# quadcopter.net
KiCad netlist of a schematic drawn in EAGLE
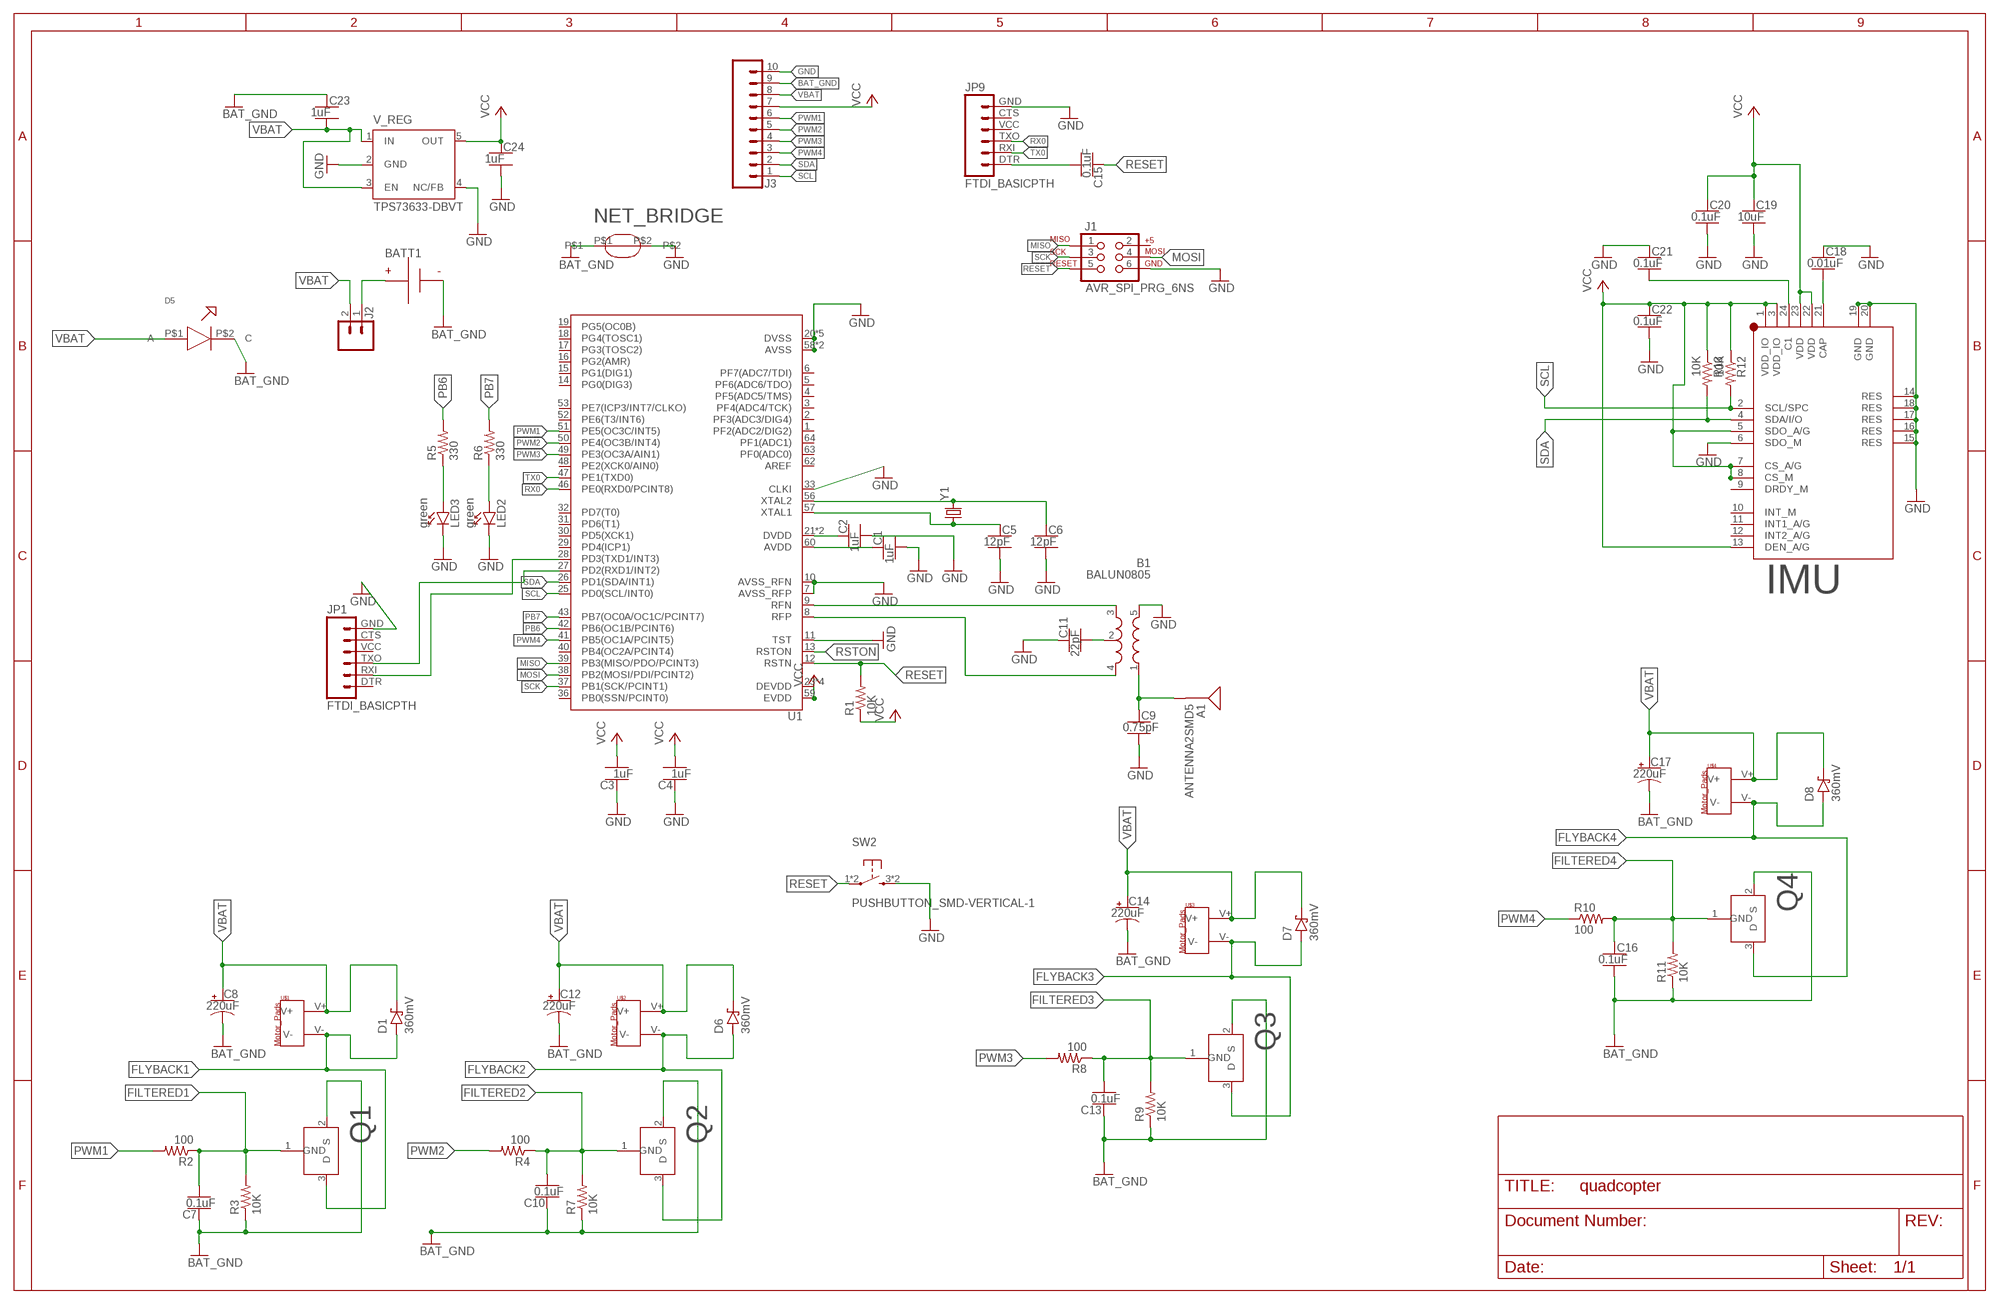
[diagram p0: schematic, sheet 1]

(export (version "E")
  (design (tool "Eeschema 10.0.6"))
  (components
    (comp (ref "A1")
      (value "ANTENNA2SMD5")
      (footprint "eagle-import:ANTENNA-CHIP5")
      (fields (field (name "MFR") "Linx Technologies Inc.") (field (name "MPN") "ANT-2.45-CHP-T"))
      (libsource (lib "eagle-import") (part "ANTENNA2SMD5"))
    )
    (comp (ref "B1")
      (value "BALUN0805")
      (footprint "eagle-import:BALUN")
      (fields (field (name "MFR") "Wurth Electronics Inc") (field (name "MPN") "748421245"))
      (libsource (lib "eagle-import") (part "BALUN0805"))
    )
    (comp (ref "BATT1")
      (value "BATTERY-HUBSAN-W/HOLDER")
      (footprint "eagle-import:BATTERY-W_HOLDER-380MAH-HUBSAN")
      (fields
        (field (name "MFR") "HUBSAN")
        (field (name "MPN") "X4-H107C-8-in-1")
        (field (name "CREATOR") "Swanson")
      )
      (libsource (lib "eagle-import") (part "BATTERY-HUBSAN-W/HOLDER"))
    )
    (comp (ref "C1")
      (value "1uF")
      (footprint "eagle-import:CAPC2012X140_HS")
      (fields
        (field (name "MFR") "Murata Electronics North America")
        (field (name "MPN") "GRM21BR71H105KA12L")
      )
      (libsource (lib "eagle-import") (part "CAPACITOR-NP_SMD-2012-0805_CERAMIC-1UF"))
    )
    (comp (ref "C2")
      (value "1uF")
      (footprint "eagle-import:CAPC2012X140_HS")
      (fields
        (field (name "MFR") "Murata Electronics North America")
        (field (name "MPN") "GRM21BR71H105KA12L")
      )
      (libsource (lib "eagle-import") (part "CAPACITOR-NP_SMD-2012-0805_CERAMIC-1UF"))
    )
    (comp (ref "C3")
      (value "1uF")
      (footprint "eagle-import:CAPC2012X140_HS")
      (fields
        (field (name "MFR") "Murata Electronics North America")
        (field (name "MPN") "GRM21BR71H105KA12L")
      )
      (libsource (lib "eagle-import") (part "CAPACITOR-NP_SMD-2012-0805_CERAMIC-1UF"))
    )
    (comp (ref "C4")
      (value "1uF")
      (footprint "eagle-import:CAPC2012X140_HS")
      (fields
        (field (name "MFR") "Murata Electronics North America")
        (field (name "MPN") "GRM21BR71H105KA12L")
      )
      (libsource (lib "eagle-import") (part "CAPACITOR-NP_SMD-2012-0805_CERAMIC-1UF"))
    )
    (comp (ref "C5")
      (value "12pF")
      (footprint "eagle-import:CAPC2012X140_HS")
      (fields
        (field (name "MFR") "Murata Electronics North America")
        (field (name "MPN") "GRM21A5C2E120JW01D")
      )
      (libsource (lib "eagle-import") (part "CAPACITOR-NP_SMD-2012-0805_CERAMIC-12PF"))
    )
    (comp (ref "C6")
      (value "12pF")
      (footprint "eagle-import:CAPC2012X140_HS")
      (fields
        (field (name "MFR") "Murata Electronics North America")
        (field (name "MPN") "GRM21A5C2E120JW01D")
      )
      (libsource (lib "eagle-import") (part "CAPACITOR-NP_SMD-2012-0805_CERAMIC-12PF"))
    )
    (comp (ref "C7")
      (value "0.1uF")
      (footprint "eagle-import:CAPC2012X140_HS")
      (fields
        (field (name "MFR") "Murata Electronics North America")
        (field (name "MPN") "GRM21BR71H104KA01L")
      )
      (libsource (lib "eagle-import") (part "CAPACITOR-NP_SMD-2012-0805_CERAMIC-0.1UF"))
    )
    (comp (ref "C8")
      (value "220uF")
      (footprint "eagle-import:CAPMP7343X310_HS")
      (fields (field (name "MFR") "AVX Corporation") (field (name "MPN") "TAJD227K006RNJ"))
      (libsource (lib "eagle-import") (part "CAPACITOR-POL_SMD-7043-D_TANTALUM-220UF"))
    )
    (comp (ref "C9")
      (value "0.75pF")
      (footprint "eagle-import:CAPC2012X140_HS")
      (fields
        (field (name "MFR") "Murata Electronics North America")
        (field (name "MPN") "GQM2195C2AR75CB01D")
      )
      (libsource (lib "eagle-import") (part "CAPACITOR-NP_SMD-2012-0805_CERAMIC-0.75PF"))
    )
    (comp (ref "C10")
      (value "0.1uF")
      (footprint "eagle-import:CAPC2012X140_HS")
      (fields
        (field (name "MFR") "Murata Electronics North America")
        (field (name "MPN") "GRM21BR71H104KA01L")
      )
      (libsource (lib "eagle-import") (part "CAPACITOR-NP_SMD-2012-0805_CERAMIC-0.1UF"))
    )
    (comp (ref "C11")
      (value "22pF")
      (footprint "eagle-import:CAPC2012X140_HS")
      (fields
        (field (name "MFR") "Murata Electronics North America")
        (field (name "MPN") "GRM21A5C2E220JW01D")
      )
      (libsource (lib "eagle-import") (part "CAPACITOR-NP_SMD-2012-0805_CERAMIC-22PF"))
    )
    (comp (ref "C12")
      (value "220uF")
      (footprint "eagle-import:CAPMP7343X310_HS")
      (fields (field (name "MFR") "AVX Corporation") (field (name "MPN") "TAJD227K006RNJ"))
      (libsource (lib "eagle-import") (part "CAPACITOR-POL_SMD-7043-D_TANTALUM-220UF"))
    )
    (comp (ref "C13")
      (value "0.1uF")
      (footprint "eagle-import:CAPC2012X140_HS")
      (fields
        (field (name "MFR") "Murata Electronics North America")
        (field (name "MPN") "GRM21BR71H104KA01L")
      )
      (libsource (lib "eagle-import") (part "CAPACITOR-NP_SMD-2012-0805_CERAMIC-0.1UF"))
    )
    (comp (ref "C14")
      (value "220uF")
      (footprint "eagle-import:CAPMP7343X310_HS")
      (fields (field (name "MFR") "AVX Corporation") (field (name "MPN") "TAJD227K006RNJ"))
      (libsource (lib "eagle-import") (part "CAPACITOR-POL_SMD-7043-D_TANTALUM-220UF"))
    )
    (comp (ref "C15")
      (value "0.1uF")
      (footprint "eagle-import:CAPC2012X140_HS")
      (fields
        (field (name "MFR") "Murata Electronics North America")
        (field (name "MPN") "GRM21BR71H104KA01L")
      )
      (libsource (lib "eagle-import") (part "CAPACITOR-NP_SMD-2012-0805_CERAMIC-0.1UF"))
    )
    (comp (ref "C16")
      (value "0.1uF")
      (footprint "eagle-import:CAPC2012X140_HS")
      (fields
        (field (name "MFR") "Murata Electronics North America")
        (field (name "MPN") "GRM21BR71H104KA01L")
      )
      (libsource (lib "eagle-import") (part "CAPACITOR-NP_SMD-2012-0805_CERAMIC-0.1UF"))
    )
    (comp (ref "C17")
      (value "220uF")
      (footprint "eagle-import:CAPMP7343X310_HS")
      (fields (field (name "MFR") "AVX Corporation") (field (name "MPN") "TAJD227K006RNJ"))
      (libsource (lib "eagle-import") (part "CAPACITOR-POL_SMD-7043-D_TANTALUM-220UF"))
    )
    (comp (ref "C18")
      (value "0.01uF")
      (footprint "eagle-import:CAPC2012X140_HS")
      (fields
        (field (name "MFR") "Murata Electronics North America")
        (field (name "MPN") "GRM2195C1H103FA01D")
      )
      (libsource (lib "eagle-import") (part "CAPACITOR-NP_SMD-2012-0805_CERAMIC-0.01UF"))
    )
    (comp (ref "C19")
      (value "10uF")
      (footprint "eagle-import:CAPC2012X140_HS")
      (fields
        (field (name "MFR") "Murata Electronics North America")
        (field (name "MPN") "GRM21BR61E106KA73L")
      )
      (libsource (lib "eagle-import") (part "CAPACITOR-NP_SMD-2012-0805_CERAMIC-10UF"))
    )
    (comp (ref "C20")
      (value "0.1uF")
      (footprint "eagle-import:CAPC2012X140_HS")
      (fields
        (field (name "MFR") "Murata Electronics North America")
        (field (name "MPN") "GRM21BR71H104KA01L")
      )
      (libsource (lib "eagle-import") (part "CAPACITOR-NP_SMD-2012-0805_CERAMIC-0.1UF"))
    )
    (comp (ref "C21")
      (value "0.1uF")
      (footprint "eagle-import:CAPC2012X140_HS")
      (fields
        (field (name "MFR") "Murata Electronics North America")
        (field (name "MPN") "GRM21BR71H104KA01L")
      )
      (libsource (lib "eagle-import") (part "CAPACITOR-NP_SMD-2012-0805_CERAMIC-0.1UF"))
    )
    (comp (ref "C22")
      (value "0.1uF")
      (footprint "eagle-import:CAPC2012X140_HS")
      (fields
        (field (name "MFR") "Murata Electronics North America")
        (field (name "MPN") "GRM21BR71H104KA01L")
      )
      (libsource (lib "eagle-import") (part "CAPACITOR-NP_SMD-2012-0805_CERAMIC-0.1UF"))
    )
    (comp (ref "C23")
      (value "1uF")
      (footprint "eagle-import:CAPC2012X140_HS")
      (fields
        (field (name "MFR") "Murata Electronics North America")
        (field (name "MPN") "GRM21BR71H105KA12L")
      )
      (libsource (lib "eagle-import") (part "CAPACITOR-NP_SMD-2012-0805_CERAMIC-1UF"))
    )
    (comp (ref "C24")
      (value "1uF")
      (footprint "eagle-import:CAPC2012X140_HS")
      (fields
        (field (name "MFR") "Murata Electronics North America")
        (field (name "MPN") "GRM21BR71H105KA12L")
      )
      (libsource (lib "eagle-import") (part "CAPACITOR-NP_SMD-2012-0805_CERAMIC-1UF"))
    )
    (comp (ref "D1")
      (value "360mV")
      (footprint "eagle-import:SOD3716X135_HS")
      (fields
        (field (name "MFR") "Toshiba Semiconductor and Storage")
        (field (name "MPN") "CRS08(TE85L,Q,M)")
      )
      (libsource (lib "eagle-import") (part "DIODE-SCHOTTKY_SMD-SOD123-360MV"))
    )
    (comp (ref "D5")
      (value "BLUE_LED")
      (footprint "eagle-import:BLUE_LED")
      (fields
        (field (name "MFR") "Everlight Electronics Co Ltd")
        (field (name "MPN") "QTLP600CBTR")
        (field (name "CREATOR") "John Wu")
        (field (name "REVIEWER") "Josh Crook")
      )
      (libsource (lib "eagle-import") (part "BLUE_LED"))
    )
    (comp (ref "D6")
      (value "360mV")
      (footprint "eagle-import:SOD3716X135_HS")
      (fields
        (field (name "MFR") "Toshiba Semiconductor and Storage")
        (field (name "MPN") "CRS08(TE85L,Q,M)")
      )
      (libsource (lib "eagle-import") (part "DIODE-SCHOTTKY_SMD-SOD123-360MV"))
    )
    (comp (ref "D7")
      (value "360mV")
      (footprint "eagle-import:SOD3716X135_HS")
      (fields
        (field (name "MFR") "Toshiba Semiconductor and Storage")
        (field (name "MPN") "CRS08(TE85L,Q,M)")
      )
      (libsource (lib "eagle-import") (part "DIODE-SCHOTTKY_SMD-SOD123-360MV"))
    )
    (comp (ref "D8")
      (value "360mV")
      (footprint "eagle-import:SOD3716X135_HS")
      (fields
        (field (name "MFR") "Toshiba Semiconductor and Storage")
        (field (name "MPN") "CRS08(TE85L,Q,M)")
      )
      (libsource (lib "eagle-import") (part "DIODE-SCHOTTKY_SMD-SOD123-360MV"))
    )
    (comp (ref "IMU")
      (value "9-AXIS_IMU")
      (footprint "eagle-import:9-AXIS_IMU")
      (fields
        (field (name "MFR") "STMicroelectronics ")
        (field (name "MPN") "LSM9DS1TR ")
        (field (name "CREATOR") "Nicholas Deagon")
        (field (name "REVIEWER") "Joshua Crook")
      )
      (libsource (lib "eagle-import") (part "9-AXIS_IMU"))
    )
    (comp (ref "J1")
      (value "AVR_SPI_PRG_6NS")
      (footprint "eagle-import:2X3-NS")
      (fields (field (name "MFR") "Amphenol FCI") (field (name "MPN") "67997-206HLF"))
      (libsource (lib "eagle-import") (part "AVR_SPI_PRG_6NS"))
    )
    (comp (ref "J2")
      (value "MALE_HEADER_2POS-2X1-0.1IN")
      (footprint "eagle-import:MALE_HEADER_2X1_0.1IN")
      (fields
        (field (name "MFR") "3M")
        (field (name "MPN") "961102-6404-AR")
        (field (name "CREATOR") "SWANSON")
      )
      (libsource (lib "eagle-import") (part "MALE_HEADER_2POS-2X1-0.1IN"))
    )
    (comp (ref "J3")
      (value "SIP-10_TH-254X10")
      (footprint "eagle-import:HDRV10W63P254_10X1_2540X254H838_HS")
      (fields (field (name "MFR") "Amphenol FCI") (field (name "MPN") "68000-110HLF"))
      (libsource (lib "eagle-import") (part "SIP-10_TH-254X10"))
    )
    (comp (ref "JP1")
      (value "FTDI_BASICPTH")
      (footprint "eagle-import:FTDI_BASIC")
      (fields (field (name "MFR") "Amphenol FCI") (field (name "MPN") "68016-406HLF"))
      (libsource (lib "eagle-import") (part "FTDI_BASICPTH"))
    )
    (comp (ref "JP9")
      (value "FTDI_BASICPTH")
      (footprint "eagle-import:FTDI_BASIC")
      (fields (field (name "MFR") "Amphenol FCI") (field (name "MPN") "68016-406HLF"))
      (libsource (lib "eagle-import") (part "FTDI_BASICPTH"))
    )
    (comp (ref "LED2")
      (value "green")
      (footprint "eagle-import:LEDSC125X200X120-2_HS")
      (fields (field (name "MFR") "Lite-On Inc") (field (name "MPN") "LTST-C170GKT"))
      (libsource (lib "eagle-import") (part "DIODE-LED_SMD-2012-0805-GREEN"))
    )
    (comp (ref "LED3")
      (value "green")
      (footprint "eagle-import:LEDSC125X200X120-2_HS")
      (fields (field (name "MFR") "Lite-On Inc") (field (name "MPN") "LTST-C170GKT"))
      (libsource (lib "eagle-import") (part "DIODE-LED_SMD-2012-0805-GREEN"))
    )
    (comp (ref "NET_BRIDGE")
      (value "NET_BRIDGE")
      (footprint "eagle-import:NET_BRIDGE")
      (fields (field (name "CREATOR") "Nicholas Deagon") (field (name "REVIEWER") "Joshua Crook"))
      (libsource (lib "eagle-import") (part "NET_BRIDGE"))
    )
    (comp (ref "Q1")
      (value "N-CHANNEL_MOSFET")
      (footprint "eagle-import:N-CHANNEL_MOSFET")
      (fields
        (field (name "MFR") "Vishay Siliconix ")
        (field (name "MPN") "SI2302CDS-T1-E3")
        (field (name "CREATOR") "Nicholas Deagon")
        (field (name "REVIEWER") "Joshua Crook")
      )
      (libsource (lib "eagle-import") (part "N-CHANNEL_MOSFET"))
    )
    (comp (ref "Q2")
      (value "N-CHANNEL_MOSFET")
      (footprint "eagle-import:N-CHANNEL_MOSFET")
      (fields
        (field (name "MFR") "Vishay Siliconix ")
        (field (name "MPN") "SI2302CDS-T1-E3")
        (field (name "CREATOR") "Nicholas Deagon")
        (field (name "REVIEWER") "Joshua Crook")
      )
      (libsource (lib "eagle-import") (part "N-CHANNEL_MOSFET"))
    )
    (comp (ref "Q3")
      (value "N-CHANNEL_MOSFET")
      (footprint "eagle-import:N-CHANNEL_MOSFET")
      (fields
        (field (name "MFR") "Vishay Siliconix ")
        (field (name "MPN") "SI2302CDS-T1-E3")
        (field (name "CREATOR") "Nicholas Deagon")
        (field (name "REVIEWER") "Joshua Crook")
      )
      (libsource (lib "eagle-import") (part "N-CHANNEL_MOSFET"))
    )
    (comp (ref "Q4")
      (value "N-CHANNEL_MOSFET")
      (footprint "eagle-import:N-CHANNEL_MOSFET")
      (fields
        (field (name "MFR") "Vishay Siliconix ")
        (field (name "MPN") "SI2302CDS-T1-E3")
        (field (name "CREATOR") "Nicholas Deagon")
        (field (name "REVIEWER") "Joshua Crook")
      )
      (libsource (lib "eagle-import") (part "N-CHANNEL_MOSFET"))
    )
    (comp (ref "R1")
      (value "10K")
      (footprint "eagle-import:RESC2012X60_HS")
      (fields (field (name "MFR") "Yageo") (field (name "MPN") "RC0805JR-0710KL"))
      (libsource (lib "eagle-import") (part "RESISTOR_SMD-2012-0805-10K"))
    )
    (comp (ref "R2")
      (value "100")
      (footprint "eagle-import:RESC2012X60_HS")
      (fields (field (name "MFR") "Yageo") (field (name "MPN") "RC0805JR-07100RL"))
      (libsource (lib "eagle-import") (part "RESISTOR_SMD-2012-0805-100"))
    )
    (comp (ref "R3")
      (value "10K")
      (footprint "eagle-import:RESC2012X60_HS")
      (fields (field (name "MFR") "Yageo") (field (name "MPN") "RC0805JR-0710KL"))
      (libsource (lib "eagle-import") (part "RESISTOR_SMD-2012-0805-10K"))
    )
    (comp (ref "R4")
      (value "100")
      (footprint "eagle-import:RESC2012X60_HS")
      (fields (field (name "MFR") "Yageo") (field (name "MPN") "RC0805JR-07100RL"))
      (libsource (lib "eagle-import") (part "RESISTOR_SMD-2012-0805-100"))
    )
    (comp (ref "R5")
      (value "330")
      (footprint "eagle-import:RESC2012X60_HS")
      (fields (field (name "MFR") "Yageo") (field (name "MPN") "RC0805JR-07330RL"))
      (libsource (lib "eagle-import") (part "RESISTOR_SMD-2012-0805-330"))
    )
    (comp (ref "R6")
      (value "330")
      (footprint "eagle-import:RESC2012X60_HS")
      (fields (field (name "MFR") "Yageo") (field (name "MPN") "RC0805JR-07330RL"))
      (libsource (lib "eagle-import") (part "RESISTOR_SMD-2012-0805-330"))
    )
    (comp (ref "R7")
      (value "10K")
      (footprint "eagle-import:RESC2012X60_HS")
      (fields (field (name "MFR") "Yageo") (field (name "MPN") "RC0805JR-0710KL"))
      (libsource (lib "eagle-import") (part "RESISTOR_SMD-2012-0805-10K"))
    )
    (comp (ref "R8")
      (value "100")
      (footprint "eagle-import:RESC2012X60_HS")
      (fields (field (name "MFR") "Yageo") (field (name "MPN") "RC0805JR-07100RL"))
      (libsource (lib "eagle-import") (part "RESISTOR_SMD-2012-0805-100"))
    )
    (comp (ref "R9")
      (value "10K")
      (footprint "eagle-import:RESC2012X60_HS")
      (fields (field (name "MFR") "Yageo") (field (name "MPN") "RC0805JR-0710KL"))
      (libsource (lib "eagle-import") (part "RESISTOR_SMD-2012-0805-10K"))
    )
    (comp (ref "R10")
      (value "100")
      (footprint "eagle-import:RESC2012X60_HS")
      (fields (field (name "MFR") "Yageo") (field (name "MPN") "RC0805JR-07100RL"))
      (libsource (lib "eagle-import") (part "RESISTOR_SMD-2012-0805-100"))
    )
    (comp (ref "R11")
      (value "10K")
      (footprint "eagle-import:RESC2012X60_HS")
      (fields (field (name "MFR") "Yageo") (field (name "MPN") "RC0805JR-0710KL"))
      (libsource (lib "eagle-import") (part "RESISTOR_SMD-2012-0805-10K"))
    )
    (comp (ref "R12")
      (value "10K")
      (footprint "eagle-import:RESC2012X60_HS")
      (fields (field (name "MFR") "Yageo") (field (name "MPN") "RC0805JR-0710KL"))
      (libsource (lib "eagle-import") (part "RESISTOR_SMD-2012-0805-10K"))
    )
    (comp (ref "R13")
      (value "10K")
      (footprint "eagle-import:RESC2012X60_HS")
      (fields (field (name "MFR") "Yageo") (field (name "MPN") "RC0805JR-0710KL"))
      (libsource (lib "eagle-import") (part "RESISTOR_SMD-2012-0805-10K"))
    )
    (comp (ref "SW2")
      (value "PUSHBUTTON_SMD-VERTICAL-1")
      (footprint "eagle-import:TE_FSM8JSMA_HS")
      (fields (field (name "MFR") "TE Connectivity Alcoswitch Switches") (field (name "MPN") "FSM4JSMA"))
      (libsource (lib "eagle-import") (part "PUSHBUTTON_SMD-VERTICAL-1"))
    )
    (comp (ref "U$1")
      (value "MOTOR_PADS")
      (footprint "eagle-import:MOTOR_PADS")
      (fields (field (name "MFR") "NA"))
      (libsource (lib "eagle-import") (part "MOTOR_PADS"))
    )
    (comp (ref "U$2")
      (value "MOTOR_PADS")
      (footprint "eagle-import:MOTOR_PADS")
      (fields (field (name "MFR") "NA"))
      (libsource (lib "eagle-import") (part "MOTOR_PADS"))
    )
    (comp (ref "U$3")
      (value "MOTOR_PADS")
      (footprint "eagle-import:MOTOR_PADS")
      (fields (field (name "MFR") "NA"))
      (libsource (lib "eagle-import") (part "MOTOR_PADS"))
    )
    (comp (ref "U$4")
      (value "MOTOR_PADS")
      (footprint "eagle-import:MOTOR_PADS")
      (fields (field (name "MFR") "NA"))
      (libsource (lib "eagle-import") (part "MOTOR_PADS"))
    )
    (comp (ref "U1")
      (value "ATMEGA128RFA1")
      (footprint "eagle-import:QFN-64")
      (fields
        (field (name "MFR") "Atmel")
        (field (name "MPN") "ATMEGA128RFA1-ZUR00")
        (field (name "CREATOR") "Swanson")
      )
      (libsource (lib "eagle-import") (part "ATMEGA128RFA1"))
    )
    (comp (ref "V_REG")
      (value "TPS73633-DBVT")
      (footprint "eagle-import:SOT23-DBV")
      (fields (field (name "MFR") "Texas Instruments") (field (name "MPN") "LP3985IM5X-3.0/NOPB"))
      (libsource (lib "eagle-import") (part "TPS73633-DBVT"))
    )
    (comp (ref "Y1")
      (value "CRYSTAL5X3")
      (footprint "eagle-import:CRYSTAL-SMD-5X3")
      (fields (field (name "MFR") "Abracon LLC") (field (name "MPN") "ABM3B-16.000MHZ-B2-T"))
      (libsource (lib "eagle-import") (part "CRYSTAL5X3"))
    )
  )
  (nets
    (net (code "1") (name "BAT_GND") (class "Default")
      (node (ref "BATT1") (pin "-") (pinfunction "N_-") (pintype "bidirectional"))
      (node (ref "C10") (pin "1") (pinfunction "1_1") (pintype "passive"))
      (node (ref "C12") (pin "2") (pinfunction "-_2") (pintype "passive"))
      (node (ref "C13") (pin "1") (pinfunction "1_1") (pintype "passive"))
      (node (ref "C14") (pin "2") (pinfunction "-_2") (pintype "passive"))
      (node (ref "C16") (pin "2") (pinfunction "2_2") (pintype "passive"))
      (node (ref "C17") (pin "2") (pinfunction "-_2") (pintype "passive"))
      (node (ref "C23") (pin "1") (pinfunction "1_1") (pintype "passive"))
      (node (ref "C7") (pin "1") (pinfunction "1_1") (pintype "passive"))
      (node (ref "C8") (pin "2") (pinfunction "-_2") (pintype "passive"))
      (node (ref "D5") (pin "P$2") (pinfunction "C_P$2") (pintype "bidirectional"))
      (node (ref "J3") (pin "9") (pinfunction "9_9") (pintype "passive"))
      (node (ref "NET_BRIDGE") (pin "P$1") (pinfunction "P$1_P$1") (pintype "bidirectional"))
      (node (ref "Q1") (pin "2") (pinfunction "S_2") (pintype "bidirectional"))
      (node (ref "Q2") (pin "2") (pinfunction "S_2") (pintype "bidirectional"))
      (node (ref "Q3") (pin "2") (pinfunction "S_2") (pintype "bidirectional"))
      (node (ref "Q4") (pin "2") (pinfunction "S_2") (pintype "bidirectional"))
      (node (ref "R11") (pin "1") (pinfunction "1_1") (pintype "passive"))
      (node (ref "R3") (pin "1") (pinfunction "1_1") (pintype "passive"))
      (node (ref "R7") (pin "1") (pinfunction "1_1") (pintype "passive"))
      (node (ref "R9") (pin "1") (pinfunction "1_1") (pintype "passive"))
    )
    (net (code "2") (name "FILTERED1") (class "Default")
      (node (ref "C7") (pin "2") (pinfunction "2_2") (pintype "passive"))
      (node (ref "Q1") (pin "1") (pinfunction "GND_1") (pintype "bidirectional"))
      (node (ref "R2") (pin "1") (pinfunction "1_1") (pintype "passive"))
      (node (ref "R3") (pin "2") (pinfunction "2_2") (pintype "passive"))
    )
    (net (code "3") (name "FILTERED2") (class "Default")
      (node (ref "C10") (pin "2") (pinfunction "2_2") (pintype "passive"))
      (node (ref "Q2") (pin "1") (pinfunction "GND_1") (pintype "bidirectional"))
      (node (ref "R4") (pin "1") (pinfunction "1_1") (pintype "passive"))
      (node (ref "R7") (pin "2") (pinfunction "2_2") (pintype "passive"))
    )
    (net (code "4") (name "FILTERED3") (class "Default")
      (node (ref "C13") (pin "2") (pinfunction "2_2") (pintype "passive"))
      (node (ref "Q3") (pin "1") (pinfunction "GND_1") (pintype "bidirectional"))
      (node (ref "R8") (pin "1") (pinfunction "1_1") (pintype "passive"))
      (node (ref "R9") (pin "2") (pinfunction "2_2") (pintype "passive"))
    )
    (net (code "5") (name "FILTERED4") (class "Default")
      (node (ref "C16") (pin "1") (pinfunction "1_1") (pintype "passive"))
      (node (ref "Q4") (pin "1") (pinfunction "GND_1") (pintype "bidirectional"))
      (node (ref "R10") (pin "2") (pinfunction "2_2") (pintype "passive"))
      (node (ref "R11") (pin "2") (pinfunction "2_2") (pintype "passive"))
    )
    (net (code "6") (name "FLYBACK1") (class "Default")
      (node (ref "D1") (pin "A") (pinfunction "A_A") (pintype "passive"))
      (node (ref "Q1") (pin "3") (pinfunction "D_3") (pintype "bidirectional"))
      (node (ref "U$1") (pin "V-") (pinfunction "V-_V-") (pintype "bidirectional"))
    )
    (net (code "7") (name "FLYBACK2") (class "Default")
      (node (ref "D6") (pin "A") (pinfunction "A_A") (pintype "passive"))
      (node (ref "Q2") (pin "3") (pinfunction "D_3") (pintype "bidirectional"))
      (node (ref "U$2") (pin "V-") (pinfunction "V-_V-") (pintype "bidirectional"))
    )
    (net (code "8") (name "FLYBACK3") (class "Default")
      (node (ref "D7") (pin "A") (pinfunction "A_A") (pintype "passive"))
      (node (ref "Q3") (pin "3") (pinfunction "D_3") (pintype "bidirectional"))
      (node (ref "U$3") (pin "V-") (pinfunction "V-_V-") (pintype "bidirectional"))
    )
    (net (code "9") (name "FLYBACK4") (class "Default")
      (node (ref "D8") (pin "A") (pinfunction "A_A") (pintype "passive"))
      (node (ref "Q4") (pin "3") (pinfunction "D_3") (pintype "bidirectional"))
      (node (ref "U$4") (pin "V-") (pinfunction "V-_V-") (pintype "bidirectional"))
    )
    (net (code "10") (name "GND") (class "Default")
      (node (ref "B1") (pin "5") (pinfunction "GND_5") (pintype "bidirectional"))
      (node (ref "C1") (pin "2") (pinfunction "2_2") (pintype "passive"))
      (node (ref "C11") (pin "1") (pinfunction "1_1") (pintype "passive"))
      (node (ref "C18") (pin "1") (pinfunction "1_1") (pintype "passive"))
      (node (ref "C19") (pin "2") (pinfunction "2_2") (pintype "passive"))
      (node (ref "C2") (pin "2") (pinfunction "2_2") (pintype "passive"))
      (node (ref "C20") (pin "2") (pinfunction "2_2") (pintype "passive"))
      (node (ref "C21") (pin "1") (pinfunction "1_1") (pintype "passive"))
      (node (ref "C22") (pin "2") (pinfunction "2_2") (pintype "passive"))
      (node (ref "C24") (pin "2") (pinfunction "2_2") (pintype "passive"))
      (node (ref "C3") (pin "1") (pinfunction "1_1") (pintype "passive"))
      (node (ref "C4") (pin "1") (pinfunction "1_1") (pintype "passive"))
      (node (ref "C5") (pin "2") (pinfunction "2_2") (pintype "passive"))
      (node (ref "C6") (pin "2") (pinfunction "2_2") (pintype "passive"))
      (node (ref "C9") (pin "2") (pinfunction "2_2") (pintype "passive"))
      (node (ref "IMU") (pin "14") (pinfunction "RES_14") (pintype "bidirectional"))
      (node (ref "IMU") (pin "15") (pinfunction "RES_15") (pintype "bidirectional"))
      (node (ref "IMU") (pin "16") (pinfunction "RES_16") (pintype "bidirectional"))
      (node (ref "IMU") (pin "17") (pinfunction "RES_17") (pintype "bidirectional"))
      (node (ref "IMU") (pin "18") (pinfunction "RES_18") (pintype "bidirectional"))
      (node (ref "IMU") (pin "19") (pinfunction "GND_19") (pintype "bidirectional"))
      (node (ref "IMU") (pin "20") (pinfunction "GND_20") (pintype "bidirectional"))
      (node (ref "IMU") (pin "6") (pinfunction "SDO_M_6") (pintype "bidirectional"))
      (node (ref "J1") (pin "6") (pinfunction "6_6") (pintype "passive"))
      (node (ref "J3") (pin "10") (pinfunction "10_10") (pintype "passive"))
      (node (ref "JP1") (pin "GND") (pinfunction "6_GND") (pintype "passive"))
      (node (ref "JP9") (pin "GND") (pinfunction "6_GND") (pintype "passive"))
      (node (ref "LED2") (pin "C") (pinfunction "C_C") (pintype "passive"))
      (node (ref "LED3") (pin "C") (pinfunction "C_C") (pintype "passive"))
      (node (ref "NET_BRIDGE") (pin "P$2") (pinfunction "P$2_P$2") (pintype "bidirectional"))
      (node (ref "SW2") (pin "3") (pinfunction "2_3") (pintype "passive"))
      (node (ref "SW2") (pin "4") (pinfunction "2_4") (pintype "passive"))
      (node (ref "U1") (pin "10") (pinfunction "AVSS_RFN_10") (pintype "bidirectional"))
      (node (ref "U1") (pin "11") (pinfunction "TST_11") (pintype "bidirectional"))
      (node (ref "U1") (pin "20") (pinfunction "DVSS_20") (pintype "bidirectional"))
      (node (ref "U1") (pin "24") (pinfunction "DVSS_24") (pintype "bidirectional"))
      (node (ref "U1") (pin "33") (pinfunction "CLKI_33") (pintype "bidirectional"))
      (node (ref "U1") (pin "35") (pinfunction "DVSS_35") (pintype "bidirectional"))
      (node (ref "U1") (pin "45") (pinfunction "DVSS_45") (pintype "bidirectional"))
      (node (ref "U1") (pin "55") (pinfunction "DVSS_55") (pintype "bidirectional"))
      (node (ref "U1") (pin "58") (pinfunction "AVSS_58") (pintype "bidirectional"))
      (node (ref "U1") (pin "61") (pinfunction "AVSS_61") (pintype "bidirectional"))
      (node (ref "U1") (pin "7") (pinfunction "AVSS_RFP_7") (pintype "bidirectional"))
      (node (ref "V_REG") (pin "2") (pinfunction "GND_2") (pintype "input"))
      (node (ref "V_REG") (pin "4") (pinfunction "NC/FB_4") (pintype "passive"))
    )
    (net (code "11") (name "MISO") (class "Default")
      (node (ref "J1") (pin "1") (pinfunction "1_1") (pintype "passive"))
      (node (ref "U1") (pin "39") (pinfunction "PB3(MISO/PDO/PCINT3)_39") (pintype "bidirectional"))
    )
    (net (code "12") (name "MOSI") (class "Default")
      (node (ref "J1") (pin "4") (pinfunction "4_4") (pintype "passive"))
      (node (ref "U1") (pin "38") (pinfunction "PB2(MOSI/PDI/PCINT2)_38") (pintype "bidirectional"))
    )
    (net (code "13") (name "Net-(A1-SIGNAL)") (class "Default")
      (node (ref "A1") (pin "FEED") (pinfunction "SIGNAL_FEED") (pintype "bidirectional"))
      (node (ref "B1") (pin "1") (pinfunction "IN_1") (pintype "bidirectional"))
      (node (ref "C9") (pin "1") (pinfunction "1_1") (pintype "passive"))
    )
    (net (code "14") (name "Net-(B1-GND-Pad2)") (class "Default")
      (node (ref "B1") (pin "2") (pinfunction "GND_2") (pintype "bidirectional"))
      (node (ref "C11") (pin "2") (pinfunction "2_2") (pintype "passive"))
    )
    (net (code "15") (name "Net-(B1-OUT1)") (class "Default")
      (node (ref "B1") (pin "4") (pinfunction "OUT1_4") (pintype "bidirectional"))
      (node (ref "U1") (pin "8") (pinfunction "RFP_8") (pintype "bidirectional"))
    )
    (net (code "16") (name "Net-(B1-OUT2)") (class "Default")
      (node (ref "B1") (pin "3") (pinfunction "OUT2_3") (pintype "bidirectional"))
      (node (ref "U1") (pin "9") (pinfunction "RFN_9") (pintype "bidirectional"))
    )
    (net (code "17") (name "Net-(BATT1-P)") (class "Default")
      (node (ref "BATT1") (pin "+") (pinfunction "P_+") (pintype "bidirectional"))
      (node (ref "J2") (pin "1") (pinfunction "1_1") (pintype "passive"))
    )
    (net (code "18") (name "Net-(C2-Pad1)") (class "Default")
      (node (ref "C2") (pin "1") (pinfunction "1_1") (pintype "passive"))
      (node (ref "U1") (pin "21") (pinfunction "DVDD_21") (pintype "bidirectional"))
      (node (ref "U1") (pin "22") (pinfunction "DVDD_22") (pintype "bidirectional"))
    )
    (net (code "19") (name "Net-(IMU-C1)") (class "Default")
      (node (ref "C21") (pin "2") (pinfunction "2_2") (pintype "passive"))
      (node (ref "IMU") (pin "24") (pinfunction "C1_24") (pintype "bidirectional"))
    )
    (net (code "20") (name "Net-(IMU-CAP)") (class "Default")
      (node (ref "C18") (pin "2") (pinfunction "2_2") (pintype "passive"))
      (node (ref "IMU") (pin "21") (pinfunction "CAP_21") (pintype "bidirectional"))
    )
    (net (code "21") (name "Net-(JP1-2)") (class "Default")
      (node (ref "JP1") (pin "RXI") (pinfunction "2_RXI") (pintype "passive"))
      (node (ref "U1") (pin "28") (pinfunction "PD3(TXD1/INT3)_28") (pintype "bidirectional"))
    )
    (net (code "22") (name "Net-(JP1-3)") (class "Default")
      (node (ref "JP1") (pin "TXO") (pinfunction "3_TXO") (pintype "passive"))
      (node (ref "U1") (pin "27") (pinfunction "PD2(RXD1/INT2)_27") (pintype "bidirectional"))
    )
    (net (code "23") (name "Net-(JP9-1)") (class "Default")
      (node (ref "C15") (pin "2") (pinfunction "2_2") (pintype "passive"))
      (node (ref "JP9") (pin "DTR") (pinfunction "1_DTR") (pintype "passive"))
    )
    (net (code "24") (name "Net-(LED2-PadA)") (class "Default")
      (node (ref "LED2") (pin "A") (pinfunction "A_A") (pintype "passive"))
      (node (ref "R6") (pin "1") (pinfunction "1_1") (pintype "passive"))
    )
    (net (code "25") (name "Net-(LED3-PadA)") (class "Default")
      (node (ref "LED3") (pin "A") (pinfunction "A_A") (pintype "passive"))
      (node (ref "R5") (pin "1") (pinfunction "1_1") (pintype "passive"))
    )
    (net (code "26") (name "Net-(U1-AVDD)") (class "Default")
      (node (ref "C1") (pin "1") (pinfunction "1_1") (pintype "passive"))
      (node (ref "U1") (pin "60") (pinfunction "AVDD_60") (pintype "bidirectional"))
    )
    (net (code "27") (name "Net-(U1-XTAL1)") (class "Default")
      (node (ref "C5") (pin "1") (pinfunction "1_1") (pintype "passive"))
      (node (ref "U1") (pin "57") (pinfunction "XTAL1_57") (pintype "bidirectional"))
      (node (ref "Y1") (pin "1") (pinfunction "1_1") (pintype "passive"))
    )
    (net (code "28") (name "Net-(U1-XTAL2)") (class "Default")
      (node (ref "C6") (pin "1") (pinfunction "1_1") (pintype "passive"))
      (node (ref "U1") (pin "56") (pinfunction "XTAL2_56") (pintype "bidirectional"))
      (node (ref "Y1") (pin "3") (pinfunction "2_3") (pintype "passive"))
    )
    (net (code "29") (name "PB6") (class "Default")
      (node (ref "R5") (pin "2") (pinfunction "2_2") (pintype "passive"))
      (node (ref "U1") (pin "42") (pinfunction "PB6(OC1B/PCINT6)_42") (pintype "bidirectional"))
    )
    (net (code "30") (name "PB7") (class "Default")
      (node (ref "R6") (pin "2") (pinfunction "2_2") (pintype "passive"))
      (node (ref "U1") (pin "43") (pinfunction "PB7(OC0A/OC1C/PCINT7)_43") (pintype "bidirectional"))
    )
    (net (code "31") (name "PWM1") (class "Default")
      (node (ref "J3") (pin "6") (pinfunction "6_6") (pintype "passive"))
      (node (ref "R2") (pin "2") (pinfunction "2_2") (pintype "passive"))
      (node (ref "U1") (pin "51") (pinfunction "PE5(OC3C/INT5)_51") (pintype "bidirectional"))
    )
    (net (code "32") (name "PWM2") (class "Default")
      (node (ref "J3") (pin "5") (pinfunction "5_5") (pintype "passive"))
      (node (ref "R4") (pin "2") (pinfunction "2_2") (pintype "passive"))
      (node (ref "U1") (pin "50") (pinfunction "PE4(OC3B/INT4)_50") (pintype "bidirectional"))
    )
    (net (code "33") (name "PWM3") (class "Default")
      (node (ref "J3") (pin "4") (pinfunction "4_4") (pintype "passive"))
      (node (ref "R8") (pin "2") (pinfunction "2_2") (pintype "passive"))
      (node (ref "U1") (pin "49") (pinfunction "PE3(OC3A/AIN1)_49") (pintype "bidirectional"))
    )
    (net (code "34") (name "PWM4") (class "Default")
      (node (ref "J3") (pin "3") (pinfunction "3_3") (pintype "passive"))
      (node (ref "R10") (pin "1") (pinfunction "1_1") (pintype "passive"))
      (node (ref "U1") (pin "41") (pinfunction "PB5(OC1A/PCINT5)_41") (pintype "bidirectional"))
    )
    (net (code "35") (name "RESET") (class "Default")
      (node (ref "C15") (pin "1") (pinfunction "1_1") (pintype "passive"))
      (node (ref "J1") (pin "5") (pinfunction "5_5") (pintype "passive"))
      (node (ref "R1") (pin "2") (pinfunction "2_2") (pintype "passive"))
      (node (ref "SW2") (pin "1") (pinfunction "1_1") (pintype "passive"))
      (node (ref "SW2") (pin "2") (pinfunction "1_2") (pintype "passive"))
      (node (ref "U1") (pin "12") (pinfunction "RSTN_12") (pintype "bidirectional"))
    )
    (net (code "36") (name "RSTON") (class "Default")
      (node (ref "U1") (pin "13") (pinfunction "RSTON_13") (pintype "bidirectional"))
    )
    (net (code "37") (name "RX0") (class "Default")
      (node (ref "JP9") (pin "TXO") (pinfunction "3_TXO") (pintype "passive"))
      (node (ref "U1") (pin "46") (pinfunction "PE0(RXD0/PCINT8)_46") (pintype "bidirectional"))
    )
    (net (code "38") (name "SCK") (class "Default")
      (node (ref "J1") (pin "3") (pinfunction "3_3") (pintype "passive"))
      (node (ref "U1") (pin "37") (pinfunction "PB1(SCK/PCINT1)_37") (pintype "bidirectional"))
    )
    (net (code "39") (name "SCL") (class "Default")
      (node (ref "IMU") (pin "2") (pinfunction "SCL/SPC_2") (pintype "bidirectional"))
      (node (ref "J3") (pin "1") (pinfunction "1_1") (pintype "passive"))
      (node (ref "R12") (pin "2") (pinfunction "2_2") (pintype "passive"))
      (node (ref "U1") (pin "25") (pinfunction "PD0(SCL/INT0)_25") (pintype "bidirectional"))
    )
    (net (code "40") (name "SDA") (class "Default")
      (node (ref "IMU") (pin "4") (pinfunction "SDA/I/O_4") (pintype "bidirectional"))
      (node (ref "J3") (pin "2") (pinfunction "2_2") (pintype "passive"))
      (node (ref "R13") (pin "2") (pinfunction "2_2") (pintype "passive"))
      (node (ref "U1") (pin "26") (pinfunction "PD1(SDA/INT1)_26") (pintype "bidirectional"))
    )
    (net (code "41") (name "TX0") (class "Default")
      (node (ref "JP9") (pin "RXI") (pinfunction "2_RXI") (pintype "passive"))
      (node (ref "U1") (pin "47") (pinfunction "PE1(TXD0)_47") (pintype "bidirectional"))
    )
    (net (code "42") (name "VBAT") (class "Default")
      (node (ref "C12") (pin "1") (pinfunction "+_1") (pintype "passive"))
      (node (ref "C14") (pin "1") (pinfunction "+_1") (pintype "passive"))
      (node (ref "C17") (pin "1") (pinfunction "+_1") (pintype "passive"))
      (node (ref "C23") (pin "2") (pinfunction "2_2") (pintype "passive"))
      (node (ref "C8") (pin "1") (pinfunction "+_1") (pintype "passive"))
      (node (ref "D1") (pin "C") (pinfunction "C_C") (pintype "passive"))
      (node (ref "D5") (pin "P$1") (pinfunction "A_P$1") (pintype "bidirectional"))
      (node (ref "D6") (pin "C") (pinfunction "C_C") (pintype "passive"))
      (node (ref "D7") (pin "C") (pinfunction "C_C") (pintype "passive"))
      (node (ref "D8") (pin "C") (pinfunction "C_C") (pintype "passive"))
      (node (ref "J2") (pin "2") (pinfunction "2_2") (pintype "passive"))
      (node (ref "J3") (pin "8") (pinfunction "8_8") (pintype "passive"))
      (node (ref "U$1") (pin "V+") (pinfunction "V+_V+") (pintype "bidirectional"))
      (node (ref "U$2") (pin "V+") (pinfunction "V+_V+") (pintype "bidirectional"))
      (node (ref "U$3") (pin "V+") (pinfunction "V+_V+") (pintype "bidirectional"))
      (node (ref "U$4") (pin "V+") (pinfunction "V+_V+") (pintype "bidirectional"))
      (node (ref "V_REG") (pin "1") (pinfunction "IN_1") (pintype "input"))
      (node (ref "V_REG") (pin "3") (pinfunction "EN_3") (pintype "input"))
    )
    (net (code "43") (name "VCC") (class "Default")
      (node (ref "C19") (pin "1") (pinfunction "1_1") (pintype "passive"))
      (node (ref "C20") (pin "1") (pinfunction "1_1") (pintype "passive"))
      (node (ref "C22") (pin "1") (pinfunction "1_1") (pintype "passive"))
      (node (ref "C24") (pin "1") (pinfunction "1_1") (pintype "passive"))
      (node (ref "C3") (pin "2") (pinfunction "2_2") (pintype "passive"))
      (node (ref "C4") (pin "2") (pinfunction "2_2") (pintype "passive"))
      (node (ref "IMU") (pin "1") (pinfunction "VDD_IO_1") (pintype "bidirectional"))
      (node (ref "IMU") (pin "13") (pinfunction "DEN_A/G_13") (pintype "bidirectional"))
      (node (ref "IMU") (pin "22") (pinfunction "VDD_22") (pintype "bidirectional"))
      (node (ref "IMU") (pin "23") (pinfunction "VDD_23") (pintype "bidirectional"))
      (node (ref "IMU") (pin "3") (pinfunction "VDD_IO_3") (pintype "bidirectional"))
      (node (ref "IMU") (pin "5") (pinfunction "SDO_A/G_5") (pintype "bidirectional"))
      (node (ref "IMU") (pin "7") (pinfunction "CS_A/G_7") (pintype "bidirectional"))
      (node (ref "IMU") (pin "8") (pinfunction "CS_M_8") (pintype "bidirectional"))
      (node (ref "J3") (pin "7") (pinfunction "7_7") (pintype "passive"))
      (node (ref "R1") (pin "1") (pinfunction "1_1") (pintype "passive"))
      (node (ref "R12") (pin "1") (pinfunction "1_1") (pintype "passive"))
      (node (ref "R13") (pin "1") (pinfunction "1_1") (pintype "passive"))
      (node (ref "U1") (pin "23") (pinfunction "DEVDD_23") (pintype "bidirectional"))
      (node (ref "U1") (pin "34") (pinfunction "DEVDD_34") (pintype "bidirectional"))
      (node (ref "U1") (pin "44") (pinfunction "DEVDD_44") (pintype "bidirectional"))
      (node (ref "U1") (pin "54") (pinfunction "DEVDD_54") (pintype "bidirectional"))
      (node (ref "U1") (pin "59") (pinfunction "EVDD_59") (pintype "bidirectional"))
      (node (ref "V_REG") (pin "5") (pinfunction "OUT_5") (pintype "passive"))
    )
    (net (code "44") (name "unconnected-(IMU-DRDY_M-Pad9)") (class "Default")
      (node (ref "IMU") (pin "9") (pinfunction "DRDY_M_9") (pintype "bidirectional"))
    )
    (net (code "45") (name "unconnected-(IMU-INT1_A{slash}G-Pad11)") (class "Default")
      (node (ref "IMU") (pin "11") (pinfunction "INT1_A/G_11") (pintype "bidirectional"))
    )
    (net (code "46") (name "unconnected-(IMU-INT2_A{slash}G-Pad12)") (class "Default")
      (node (ref "IMU") (pin "12") (pinfunction "INT2_A/G_12") (pintype "bidirectional"))
    )
    (net (code "47") (name "unconnected-(IMU-INT_M-Pad10)") (class "Default")
      (node (ref "IMU") (pin "10") (pinfunction "INT_M_10") (pintype "bidirectional"))
    )
    (net (code "48") (name "unconnected-(J1-Pad2)") (class "Default")
      (node (ref "J1") (pin "2") (pinfunction "2_2") (pintype "passive"))
    )
    (net (code "49") (name "unconnected-(JP1-1-PadDTR)") (class "Default")
      (node (ref "JP1") (pin "DTR") (pinfunction "1_DTR") (pintype "passive"))
    )
    (net (code "50") (name "unconnected-(JP1-4-PadVCC)") (class "Default")
      (node (ref "JP1") (pin "VCC") (pinfunction "4_VCC") (pintype "passive"))
    )
    (net (code "51") (name "unconnected-(JP1-5-PadCTS)") (class "Default")
      (node (ref "JP1") (pin "CTS") (pinfunction "5_CTS") (pintype "passive"))
    )
    (net (code "52") (name "unconnected-(JP9-4-PadVCC)") (class "Default")
      (node (ref "JP9") (pin "VCC") (pinfunction "4_VCC") (pintype "passive"))
    )
    (net (code "53") (name "unconnected-(JP9-5-PadCTS)") (class "Default")
      (node (ref "JP9") (pin "CTS") (pinfunction "5_CTS") (pintype "passive"))
    )
    (net (code "54") (name "unconnected-(U1-AREF-Pad62)") (class "Default")
      (node (ref "U1") (pin "62") (pinfunction "AREF_62") (pintype "bidirectional"))
    )
    (net (code "55") (name "unconnected-(U1-PB0(SSN{slash}PCINT0)-Pad36)") (class "Default")
      (node (ref "U1") (pin "36") (pinfunction "PB0(SSN/PCINT0)_36") (pintype "bidirectional"))
    )
    (net (code "56") (name "unconnected-(U1-PB4(OC2A{slash}PCINT4)-Pad40)") (class "Default")
      (node (ref "U1") (pin "40") (pinfunction "PB4(OC2A/PCINT4)_40") (pintype "bidirectional"))
    )
    (net (code "57") (name "unconnected-(U1-PD4(ICP1)-Pad29)") (class "Default")
      (node (ref "U1") (pin "29") (pinfunction "PD4(ICP1)_29") (pintype "bidirectional"))
    )
    (net (code "58") (name "unconnected-(U1-PD5(XCK1)-Pad30)") (class "Default")
      (node (ref "U1") (pin "30") (pinfunction "PD5(XCK1)_30") (pintype "bidirectional"))
    )
    (net (code "59") (name "unconnected-(U1-PD6(T1)-Pad31)") (class "Default")
      (node (ref "U1") (pin "31") (pinfunction "PD6(T1)_31") (pintype "bidirectional"))
    )
    (net (code "60") (name "unconnected-(U1-PD7(T0)-Pad32)") (class "Default")
      (node (ref "U1") (pin "32") (pinfunction "PD7(T0)_32") (pintype "bidirectional"))
    )
    (net (code "61") (name "unconnected-(U1-PE2(XCK0{slash}AIN0)-Pad48)") (class "Default")
      (node (ref "U1") (pin "48") (pinfunction "PE2(XCK0/AIN0)_48") (pintype "bidirectional"))
    )
    (net (code "62") (name "unconnected-(U1-PE6(T3{slash}INT6)-Pad52)") (class "Default")
      (node (ref "U1") (pin "52") (pinfunction "PE6(T3/INT6)_52") (pintype "bidirectional"))
    )
    (net (code "63") (name "unconnected-(U1-PE7(ICP3{slash}INT7{slash}CLKO)-Pad53)") (class "Default")
      (node (ref "U1") (pin "53") (pinfunction "PE7(ICP3/INT7/CLKO)_53") (pintype "bidirectional"))
    )
    (net (code "64") (name "unconnected-(U1-PF0(ADC0)-Pad63)") (class "Default")
      (node (ref "U1") (pin "63") (pinfunction "PF0(ADC0)_63") (pintype "bidirectional"))
    )
    (net (code "65") (name "unconnected-(U1-PF1(ADC1)-Pad64)") (class "Default")
      (node (ref "U1") (pin "64") (pinfunction "PF1(ADC1)_64") (pintype "bidirectional"))
    )
    (net (code "66") (name "unconnected-(U1-PF2(ADC2{slash}DIG2)-Pad1)") (class "Default")
      (node (ref "U1") (pin "1") (pinfunction "PF2(ADC2/DIG2)_1") (pintype "bidirectional"))
    )
    (net (code "67") (name "unconnected-(U1-PF3(ADC3{slash}DIG4)-Pad2)") (class "Default")
      (node (ref "U1") (pin "2") (pinfunction "PF3(ADC3/DIG4)_2") (pintype "bidirectional"))
    )
    (net (code "68") (name "unconnected-(U1-PF4(ADC4{slash}TCK)-Pad3)") (class "Default")
      (node (ref "U1") (pin "3") (pinfunction "PF4(ADC4/TCK)_3") (pintype "bidirectional"))
    )
    (net (code "69") (name "unconnected-(U1-PF5(ADC5{slash}TMS)-Pad4)") (class "Default")
      (node (ref "U1") (pin "4") (pinfunction "PF5(ADC5/TMS)_4") (pintype "bidirectional"))
    )
    (net (code "70") (name "unconnected-(U1-PF6(ADC6{slash}TDO)-Pad5)") (class "Default")
      (node (ref "U1") (pin "5") (pinfunction "PF6(ADC6/TDO)_5") (pintype "bidirectional"))
    )
    (net (code "71") (name "unconnected-(U1-PF7(ADC7{slash}TDI)-Pad6)") (class "Default")
      (node (ref "U1") (pin "6") (pinfunction "PF7(ADC7/TDI)_6") (pintype "bidirectional"))
    )
    (net (code "72") (name "unconnected-(U1-PG0(DIG3)-Pad14)") (class "Default")
      (node (ref "U1") (pin "14") (pinfunction "PG0(DIG3)_14") (pintype "bidirectional"))
    )
    (net (code "73") (name "unconnected-(U1-PG1(DIG1)-Pad15)") (class "Default")
      (node (ref "U1") (pin "15") (pinfunction "PG1(DIG1)_15") (pintype "bidirectional"))
    )
    (net (code "74") (name "unconnected-(U1-PG2(AMR)-Pad16)") (class "Default")
      (node (ref "U1") (pin "16") (pinfunction "PG2(AMR)_16") (pintype "bidirectional"))
    )
    (net (code "75") (name "unconnected-(U1-PG3(TOSC2)-Pad17)") (class "Default")
      (node (ref "U1") (pin "17") (pinfunction "PG3(TOSC2)_17") (pintype "bidirectional"))
    )
    (net (code "76") (name "unconnected-(U1-PG4(TOSC1)-Pad18)") (class "Default")
      (node (ref "U1") (pin "18") (pinfunction "PG4(TOSC1)_18") (pintype "bidirectional"))
    )
    (net (code "77") (name "unconnected-(U1-PG5(OC0B)-Pad19)") (class "Default")
      (node (ref "U1") (pin "19") (pinfunction "PG5(OC0B)_19") (pintype "bidirectional"))
    )
  )
)
